# Saturn_Cartage.net
KiCad netlist of a schematic drawn in Altium Designer
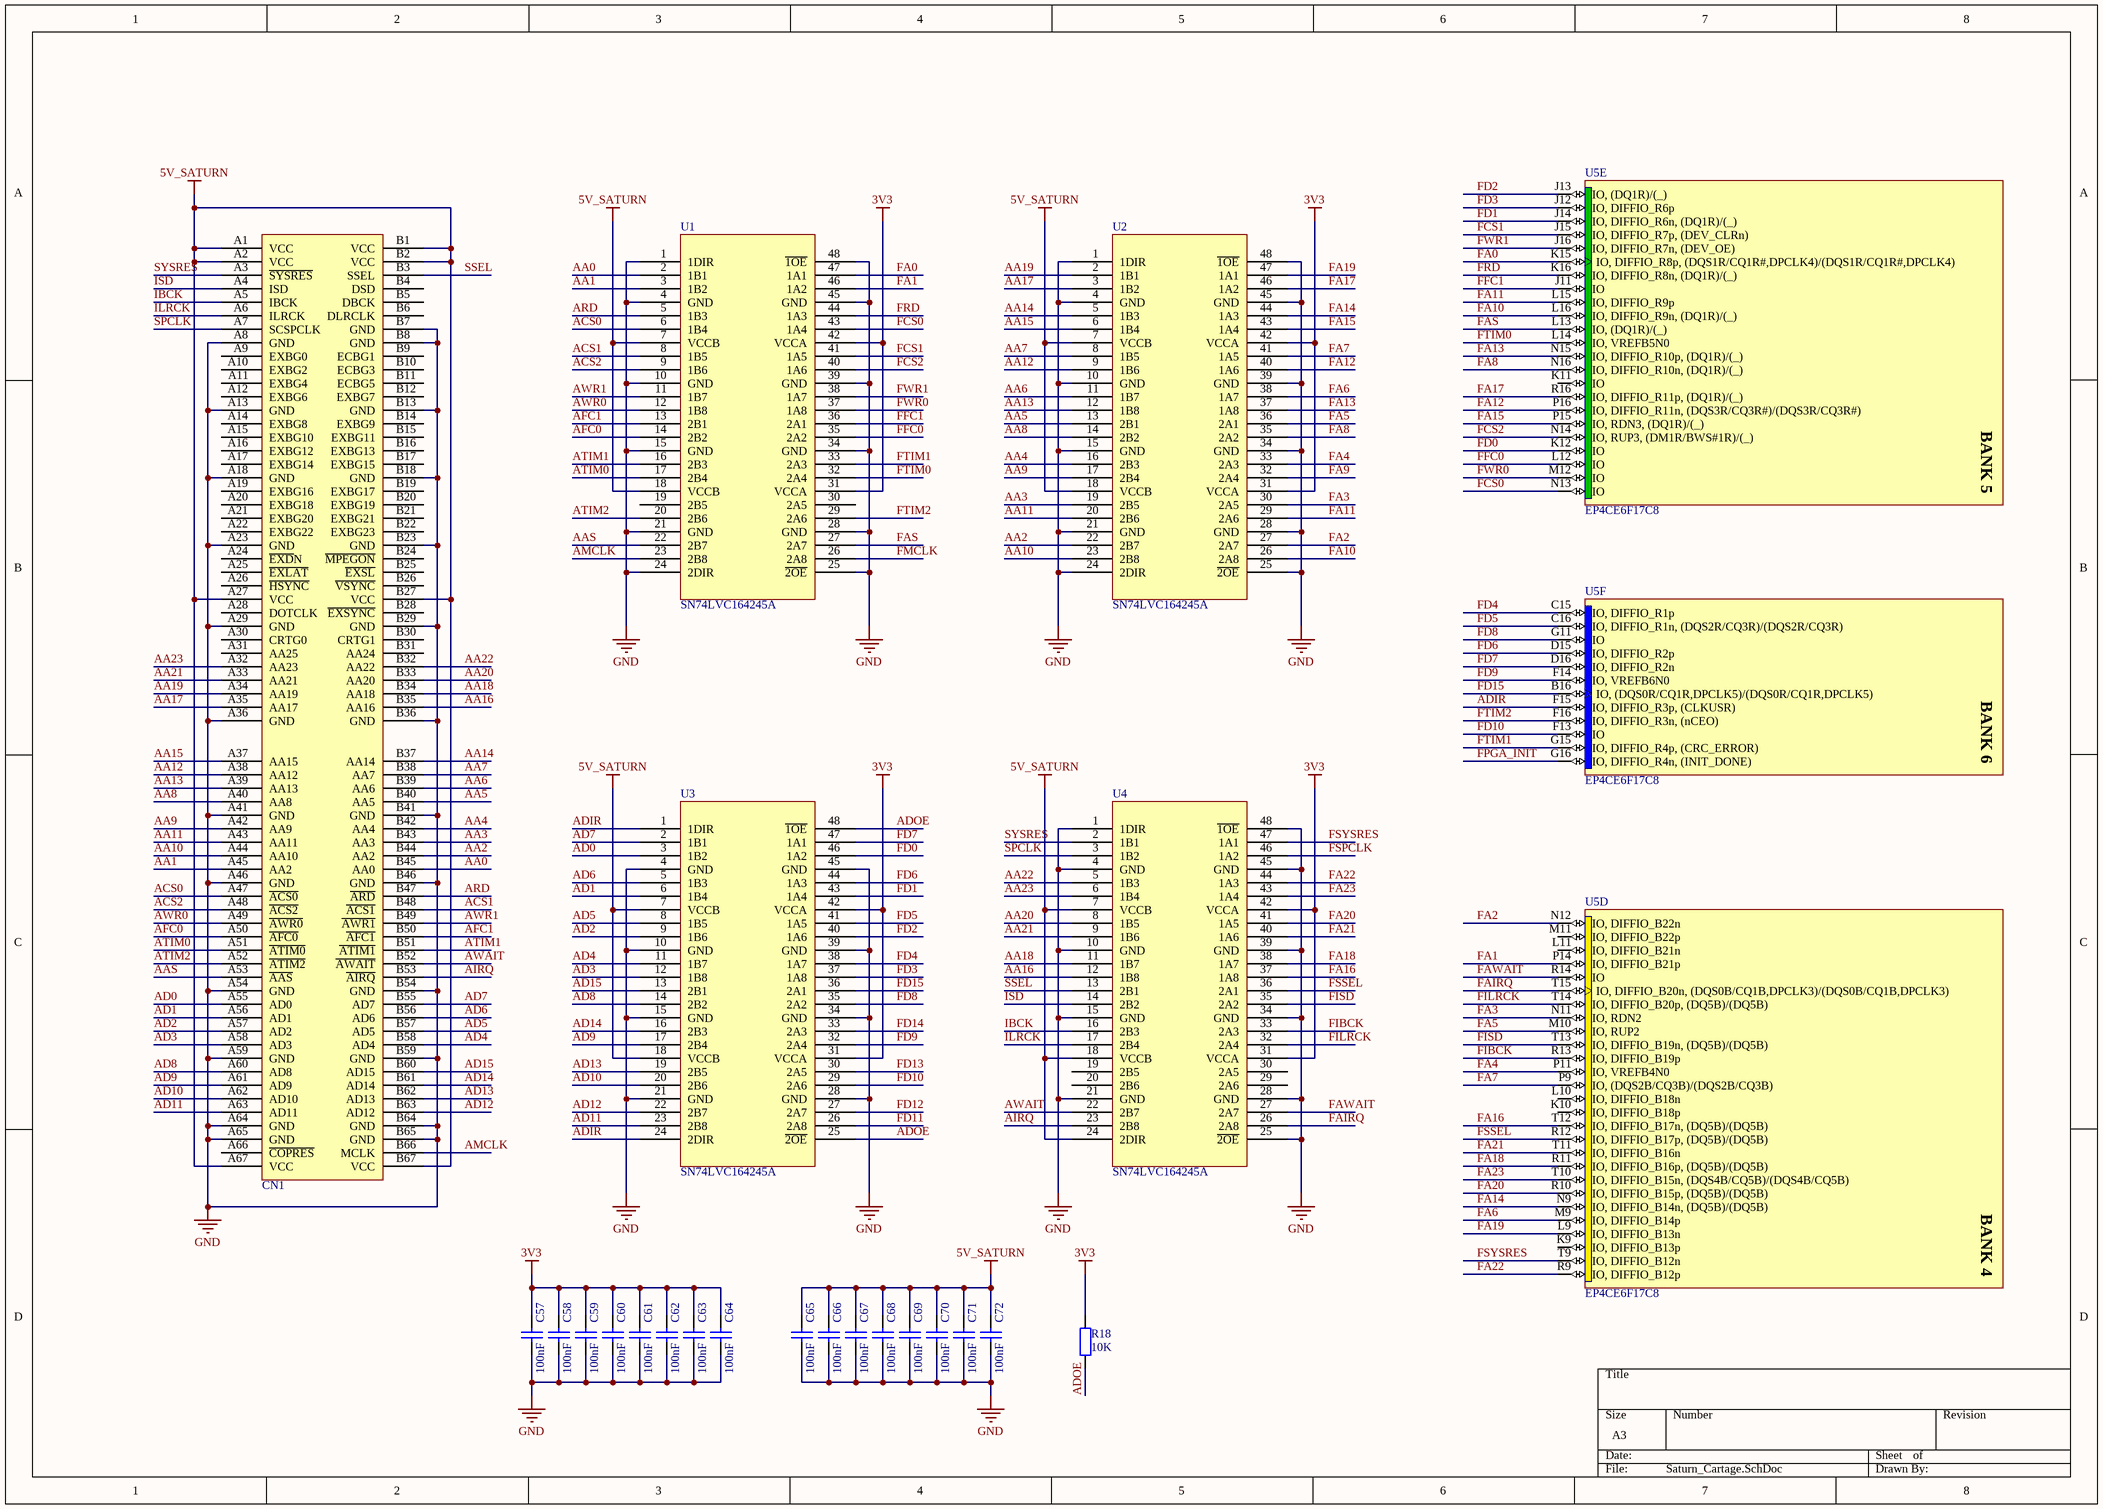
[diagram p0: Saturn_Cartage.SchDoc]

(export (version "E")
  (design (tool "Eeschema 10.0.6"))
  (components
    (comp (ref "C57")
      (value "100nF")
      (footprint "C0603")
      (description "Capacitor")
      (fields (field (name "PUBLISHER") "Altium Limited"))
      (libsource (lib "Miscellaneous Devices") (part "Cap"))
    )
    (comp (ref "C58")
      (value "100nF")
      (footprint "C0603")
      (description "Capacitor")
      (fields (field (name "PUBLISHER") "Altium Limited"))
      (libsource (lib "Miscellaneous Devices") (part "Cap"))
    )
    (comp (ref "C59")
      (value "100nF")
      (footprint "C0603")
      (description "Capacitor")
      (fields (field (name "PUBLISHER") "Altium Limited"))
      (libsource (lib "Miscellaneous Devices") (part "Cap"))
    )
    (comp (ref "C60")
      (value "100nF")
      (footprint "C0603")
      (description "Capacitor")
      (fields (field (name "PUBLISHER") "Altium Limited"))
      (libsource (lib "Miscellaneous Devices") (part "Cap"))
    )
    (comp (ref "C61")
      (value "100nF")
      (footprint "C0603")
      (description "Capacitor")
      (fields (field (name "PUBLISHER") "Altium Limited"))
      (libsource (lib "Miscellaneous Devices") (part "Cap"))
    )
    (comp (ref "C62")
      (value "100nF")
      (footprint "C0603")
      (description "Capacitor")
      (fields (field (name "PUBLISHER") "Altium Limited"))
      (libsource (lib "Miscellaneous Devices") (part "Cap"))
    )
    (comp (ref "C63")
      (value "100nF")
      (footprint "C0603")
      (description "Capacitor")
      (fields (field (name "PUBLISHER") "Altium Limited"))
      (libsource (lib "Miscellaneous Devices") (part "Cap"))
    )
    (comp (ref "C64")
      (value "100nF")
      (footprint "C0603")
      (description "Capacitor")
      (fields (field (name "PUBLISHER") "Altium Limited"))
      (libsource (lib "Miscellaneous Devices") (part "Cap"))
    )
    (comp (ref "C65")
      (value "100nF")
      (footprint "C0603")
      (description "Capacitor")
      (fields (field (name "PUBLISHER") "Altium Limited"))
      (libsource (lib "Miscellaneous Devices") (part "Cap"))
    )
    (comp (ref "C66")
      (value "100nF")
      (footprint "C0603")
      (description "Capacitor")
      (fields (field (name "PUBLISHER") "Altium Limited"))
      (libsource (lib "Miscellaneous Devices") (part "Cap"))
    )
    (comp (ref "C67")
      (value "100nF")
      (footprint "C0603")
      (description "Capacitor")
      (fields (field (name "PUBLISHER") "Altium Limited"))
      (libsource (lib "Miscellaneous Devices") (part "Cap"))
    )
    (comp (ref "C68")
      (value "100nF")
      (footprint "C0603")
      (description "Capacitor")
      (fields (field (name "PUBLISHER") "Altium Limited"))
      (libsource (lib "Miscellaneous Devices") (part "Cap"))
    )
    (comp (ref "C69")
      (value "100nF")
      (footprint "C0603")
      (description "Capacitor")
      (fields (field (name "PUBLISHER") "Altium Limited"))
      (libsource (lib "Miscellaneous Devices") (part "Cap"))
    )
    (comp (ref "C70")
      (value "100nF")
      (footprint "C0603")
      (description "Capacitor")
      (fields (field (name "PUBLISHER") "Altium Limited"))
      (libsource (lib "Miscellaneous Devices") (part "Cap"))
    )
    (comp (ref "C71")
      (value "100nF")
      (footprint "C0603")
      (description "Capacitor")
      (fields (field (name "PUBLISHER") "Altium Limited"))
      (libsource (lib "Miscellaneous Devices") (part "Cap"))
    )
    (comp (ref "C72")
      (value "100nF")
      (footprint "C0603")
      (description "Capacitor")
      (fields (field (name "PUBLISHER") "Altium Limited"))
      (libsource (lib "Miscellaneous Devices") (part "Cap"))
    )
    (comp (ref "CN1")
      (value "SaturnCartage")
      (footprint "Saturn_cart")
      (libsource (lib "ssmaster_1") (part "SaturnCartage"))
    )
    (comp (ref "R18")
      (value "10K")
      (footprint "R0603")
      (description "Resistor")
      (fields (field (name "PUBLISHER") "Altium Limited"))
      (libsource (lib "Miscellaneous Devices") (part "Res2"))
    )
    (comp (ref "U1")
      (value "SN74LVC164245A")
      (footprint "DGG048")
      (libsource (lib "ssmaster_1") (part "SN74LVC164245A"))
    )
    (comp (ref "U2")
      (value "SN74LVC164245A")
      (footprint "DGG048")
      (libsource (lib "ssmaster_1") (part "SN74LVC164245A"))
    )
    (comp (ref "U3")
      (value "SN74LVC164245A")
      (footprint "DGG048")
      (libsource (lib "ssmaster_1") (part "SN74LVC164245A"))
    )
    (comp (ref "U4")
      (value "SN74LVC164245A")
      (footprint "DGG048")
      (libsource (lib "ssmaster_1") (part "SN74LVC164245A"))
    )
    (comp (ref "U5")
      (value "EP4CE6F17C8")
      (footprint "FBGA256")
      (fields (field (name "PUBLISHER") "Altium Limited"))
      (libsource (lib "Altera Cyclone IV E") (part "EP4CE6F17C8"))
    )
  )
  (nets
    (net (code "1") (name "/AA0") (class "Default")
      (node (ref "CN1") (pin "B45") (pinfunction "AA0_B45") (pintype "passive"))
      (node (ref "U1") (pin "2") (pinfunction "1B1_2") (pintype "passive"))
    )
    (net (code "2") (name "/AA1") (class "Default")
      (node (ref "CN1") (pin "A45") (pinfunction "AA2_A45") (pintype "passive"))
      (node (ref "U1") (pin "3") (pinfunction "1B2_3") (pintype "passive"))
    )
    (net (code "3") (name "/AA2") (class "Default")
      (node (ref "CN1") (pin "B44") (pinfunction "AA2_B44") (pintype "passive"))
      (node (ref "U2") (pin "22") (pinfunction "2B7_22") (pintype "passive"))
    )
    (net (code "4") (name "/AA3") (class "Default")
      (node (ref "CN1") (pin "B43") (pinfunction "AA3_B43") (pintype "passive"))
      (node (ref "U2") (pin "19") (pinfunction "2B5_19") (pintype "passive"))
    )
    (net (code "5") (name "/AA4") (class "Default")
      (node (ref "CN1") (pin "B42") (pinfunction "AA4_B42") (pintype "passive"))
      (node (ref "U2") (pin "16") (pinfunction "2B3_16") (pintype "passive"))
    )
    (net (code "6") (name "/AA5") (class "Default")
      (node (ref "CN1") (pin "B40") (pinfunction "AA5_B40") (pintype "passive"))
      (node (ref "U2") (pin "13") (pinfunction "2B1_13") (pintype "passive"))
    )
    (net (code "7") (name "/AA6") (class "Default")
      (node (ref "CN1") (pin "B39") (pinfunction "AA6_B39") (pintype "passive"))
      (node (ref "U2") (pin "11") (pinfunction "1B7_11") (pintype "passive"))
    )
    (net (code "8") (name "/AA7") (class "Default")
      (node (ref "CN1") (pin "B38") (pinfunction "AA7_B38") (pintype "passive"))
      (node (ref "U2") (pin "8") (pinfunction "1B5_8") (pintype "passive"))
    )
    (net (code "9") (name "/AA8") (class "Default")
      (node (ref "CN1") (pin "A40") (pinfunction "AA8_A40") (pintype "passive"))
      (node (ref "U2") (pin "14") (pinfunction "2B2_14") (pintype "passive"))
    )
    (net (code "10") (name "/AA9") (class "Default")
      (node (ref "CN1") (pin "A42") (pinfunction "AA9_A42") (pintype "passive"))
      (node (ref "U2") (pin "17") (pinfunction "2B4_17") (pintype "passive"))
    )
    (net (code "11") (name "/AA10") (class "Default")
      (node (ref "CN1") (pin "A44") (pinfunction "AA10_A44") (pintype "passive"))
      (node (ref "U2") (pin "23") (pinfunction "2B8_23") (pintype "passive"))
    )
    (net (code "12") (name "/AA11") (class "Default")
      (node (ref "CN1") (pin "A43") (pinfunction "AA11_A43") (pintype "passive"))
      (node (ref "U2") (pin "20") (pinfunction "2B6_20") (pintype "passive"))
    )
    (net (code "13") (name "/AA12") (class "Default")
      (node (ref "CN1") (pin "A38") (pinfunction "AA12_A38") (pintype "passive"))
      (node (ref "U2") (pin "9") (pinfunction "1B6_9") (pintype "passive"))
    )
    (net (code "14") (name "/AA13") (class "Default")
      (node (ref "CN1") (pin "A39") (pinfunction "AA13_A39") (pintype "passive"))
      (node (ref "U2") (pin "12") (pinfunction "1B8_12") (pintype "passive"))
    )
    (net (code "15") (name "/AA14") (class "Default")
      (node (ref "CN1") (pin "B37") (pinfunction "AA14_B37") (pintype "passive"))
      (node (ref "U2") (pin "5") (pinfunction "1B3_5") (pintype "passive"))
    )
    (net (code "16") (name "/AA15") (class "Default")
      (node (ref "CN1") (pin "A37") (pinfunction "AA15_A37") (pintype "passive"))
      (node (ref "U2") (pin "6") (pinfunction "1B4_6") (pintype "passive"))
    )
    (net (code "17") (name "/AA16") (class "Default")
      (node (ref "CN1") (pin "B35") (pinfunction "AA16_B35") (pintype "passive"))
      (node (ref "U4") (pin "12") (pinfunction "1B8_12") (pintype "passive"))
    )
    (net (code "18") (name "/AA17") (class "Default")
      (node (ref "CN1") (pin "A35") (pinfunction "AA17_A35") (pintype "passive"))
      (node (ref "U2") (pin "3") (pinfunction "1B2_3") (pintype "passive"))
    )
    (net (code "19") (name "/AA18") (class "Default")
      (node (ref "CN1") (pin "B34") (pinfunction "AA18_B34") (pintype "passive"))
      (node (ref "U4") (pin "11") (pinfunction "1B7_11") (pintype "passive"))
    )
    (net (code "20") (name "/AA19") (class "Default")
      (node (ref "CN1") (pin "A34") (pinfunction "AA19_A34") (pintype "passive"))
      (node (ref "U2") (pin "2") (pinfunction "1B1_2") (pintype "passive"))
    )
    (net (code "21") (name "/AA20") (class "Default")
      (node (ref "CN1") (pin "B33") (pinfunction "AA20_B33") (pintype "passive"))
      (node (ref "U4") (pin "8") (pinfunction "1B5_8") (pintype "passive"))
    )
    (net (code "22") (name "/AA21") (class "Default")
      (node (ref "CN1") (pin "A33") (pinfunction "AA21_A33") (pintype "passive"))
      (node (ref "U4") (pin "9") (pinfunction "1B6_9") (pintype "passive"))
    )
    (net (code "23") (name "/AA22") (class "Default")
      (node (ref "CN1") (pin "B32") (pinfunction "AA22_B32") (pintype "passive"))
      (node (ref "U4") (pin "5") (pinfunction "1B3_5") (pintype "passive"))
    )
    (net (code "24") (name "/AA23") (class "Default")
      (node (ref "CN1") (pin "A32") (pinfunction "AA23_A32") (pintype "passive"))
      (node (ref "U4") (pin "6") (pinfunction "1B4_6") (pintype "passive"))
    )
    (net (code "25") (name "/AAS") (class "Default")
      (node (ref "CN1") (pin "A53") (pinfunction "~{AAS}_A53") (pintype "passive"))
      (node (ref "U1") (pin "22") (pinfunction "2B7_22") (pintype "passive"))
    )
    (net (code "26") (name "/ACS0") (class "Default")
      (node (ref "CN1") (pin "A47") (pinfunction "~{ACS0}_A47") (pintype "passive"))
      (node (ref "U1") (pin "6") (pinfunction "1B4_6") (pintype "passive"))
    )
    (net (code "27") (name "/ACS1") (class "Default")
      (node (ref "CN1") (pin "B48") (pinfunction "~{ACS1}_B48") (pintype "passive"))
      (node (ref "U1") (pin "8") (pinfunction "1B5_8") (pintype "passive"))
    )
    (net (code "28") (name "/ACS2") (class "Default")
      (node (ref "CN1") (pin "A48") (pinfunction "~{ACS2}_A48") (pintype "passive"))
      (node (ref "U1") (pin "9") (pinfunction "1B6_9") (pintype "passive"))
    )
    (net (code "29") (name "/AD0") (class "Default")
      (node (ref "CN1") (pin "A55") (pinfunction "AD0_A55") (pintype "passive"))
      (node (ref "U3") (pin "3") (pinfunction "1B2_3") (pintype "passive"))
    )
    (net (code "30") (name "/AD1") (class "Default")
      (node (ref "CN1") (pin "A56") (pinfunction "AD1_A56") (pintype "passive"))
      (node (ref "U3") (pin "6") (pinfunction "1B4_6") (pintype "passive"))
    )
    (net (code "31") (name "/AD2") (class "Default")
      (node (ref "CN1") (pin "A57") (pinfunction "AD2_A57") (pintype "passive"))
      (node (ref "U3") (pin "9") (pinfunction "1B6_9") (pintype "passive"))
    )
    (net (code "32") (name "/AD3") (class "Default")
      (node (ref "CN1") (pin "A58") (pinfunction "AD3_A58") (pintype "passive"))
      (node (ref "U3") (pin "12") (pinfunction "1B8_12") (pintype "passive"))
    )
    (net (code "33") (name "/AD4") (class "Default")
      (node (ref "CN1") (pin "B58") (pinfunction "AD4_B58") (pintype "passive"))
      (node (ref "U3") (pin "11") (pinfunction "1B7_11") (pintype "passive"))
    )
    (net (code "34") (name "/AD5") (class "Default")
      (node (ref "CN1") (pin "B57") (pinfunction "AD5_B57") (pintype "passive"))
      (node (ref "U3") (pin "8") (pinfunction "1B5_8") (pintype "passive"))
    )
    (net (code "35") (name "/AD6") (class "Default")
      (node (ref "CN1") (pin "B56") (pinfunction "AD6_B56") (pintype "passive"))
      (node (ref "U3") (pin "5") (pinfunction "1B3_5") (pintype "passive"))
    )
    (net (code "36") (name "/AD7") (class "Default")
      (node (ref "CN1") (pin "B55") (pinfunction "AD7_B55") (pintype "passive"))
      (node (ref "U3") (pin "2") (pinfunction "1B1_2") (pintype "passive"))
    )
    (net (code "37") (name "/AD8") (class "Default")
      (node (ref "CN1") (pin "A60") (pinfunction "AD8_A60") (pintype "passive"))
      (node (ref "U3") (pin "14") (pinfunction "2B2_14") (pintype "passive"))
    )
    (net (code "38") (name "/AD9") (class "Default")
      (node (ref "CN1") (pin "A61") (pinfunction "AD9_A61") (pintype "passive"))
      (node (ref "U3") (pin "17") (pinfunction "2B4_17") (pintype "passive"))
    )
    (net (code "39") (name "/AD10") (class "Default")
      (node (ref "CN1") (pin "A62") (pinfunction "AD10_A62") (pintype "passive"))
      (node (ref "U3") (pin "20") (pinfunction "2B6_20") (pintype "passive"))
    )
    (net (code "40") (name "/AD11") (class "Default")
      (node (ref "CN1") (pin "A63") (pinfunction "AD11_A63") (pintype "passive"))
      (node (ref "U3") (pin "23") (pinfunction "2B8_23") (pintype "passive"))
    )
    (net (code "41") (name "/AD12") (class "Default")
      (node (ref "CN1") (pin "B63") (pinfunction "AD12_B63") (pintype "passive"))
      (node (ref "U3") (pin "22") (pinfunction "2B7_22") (pintype "passive"))
    )
    (net (code "42") (name "/AD13") (class "Default")
      (node (ref "CN1") (pin "B62") (pinfunction "AD13_B62") (pintype "passive"))
      (node (ref "U3") (pin "19") (pinfunction "2B5_19") (pintype "passive"))
    )
    (net (code "43") (name "/AD14") (class "Default")
      (node (ref "CN1") (pin "B61") (pinfunction "AD14_B61") (pintype "passive"))
      (node (ref "U3") (pin "16") (pinfunction "2B3_16") (pintype "passive"))
    )
    (net (code "44") (name "/AD15") (class "Default")
      (node (ref "CN1") (pin "B60") (pinfunction "AD15_B60") (pintype "passive"))
      (node (ref "U3") (pin "13") (pinfunction "2B1_13") (pintype "passive"))
    )
    (net (code "45") (name "/ADIR") (class "Default")
      (node (ref "U3") (pin "1") (pinfunction "1DIR_1") (pintype "passive"))
      (node (ref "U3") (pin "24") (pinfunction "2DIR_24") (pintype "passive"))
      (node (ref "U5") (pin "F15") (pinfunction "IO,_DIFFIO_R3p,_(CLKUSR)_F15") (pintype "bidirectional"))
    )
    (net (code "46") (name "/ADOE") (class "Default")
      (node (ref "R18") (pin "1") (pinfunction "1_1") (pintype "passive"))
      (node (ref "U3") (pin "25") (pinfunction "~{2OE}_25") (pintype "passive"))
      (node (ref "U3") (pin "48") (pinfunction "~{1OE}_48") (pintype "passive"))
    )
    (net (code "47") (name "/AFC0") (class "Default")
      (node (ref "CN1") (pin "A50") (pinfunction "~{AFC0}_A50") (pintype "passive"))
      (node (ref "U1") (pin "14") (pinfunction "2B2_14") (pintype "passive"))
    )
    (net (code "48") (name "/AFC1") (class "Default")
      (node (ref "CN1") (pin "B50") (pinfunction "~{AFC1}_B50") (pintype "passive"))
      (node (ref "U1") (pin "13") (pinfunction "2B1_13") (pintype "passive"))
    )
    (net (code "49") (name "/AIRQ") (class "Default")
      (node (ref "CN1") (pin "B53") (pinfunction "~{AIRQ}_B53") (pintype "passive"))
      (node (ref "U4") (pin "23") (pinfunction "2B8_23") (pintype "passive"))
    )
    (net (code "50") (name "/AMCLK") (class "Default")
      (node (ref "CN1") (pin "B66") (pinfunction "MCLK_B66") (pintype "passive"))
      (node (ref "U1") (pin "23") (pinfunction "2B8_23") (pintype "passive"))
    )
    (net (code "51") (name "/ARD") (class "Default")
      (node (ref "CN1") (pin "B47") (pinfunction "~{ARD}_B47") (pintype "passive"))
      (node (ref "U1") (pin "5") (pinfunction "1B3_5") (pintype "passive"))
    )
    (net (code "52") (name "/ATIM0") (class "Default")
      (node (ref "CN1") (pin "A51") (pinfunction "~{ATIM0}_A51") (pintype "passive"))
      (node (ref "U1") (pin "17") (pinfunction "2B4_17") (pintype "passive"))
    )
    (net (code "53") (name "/ATIM1") (class "Default")
      (node (ref "CN1") (pin "B51") (pinfunction "~{ATIM1}_B51") (pintype "passive"))
      (node (ref "U1") (pin "16") (pinfunction "2B3_16") (pintype "passive"))
    )
    (net (code "54") (name "/ATIM2") (class "Default")
      (node (ref "CN1") (pin "A52") (pinfunction "~{ATIM2}_A52") (pintype "passive"))
      (node (ref "U1") (pin "20") (pinfunction "2B6_20") (pintype "passive"))
    )
    (net (code "55") (name "/AWAIT") (class "Default")
      (node (ref "CN1") (pin "B52") (pinfunction "~{AWAIT}_B52") (pintype "passive"))
      (node (ref "U4") (pin "22") (pinfunction "2B7_22") (pintype "passive"))
    )
    (net (code "56") (name "/AWR0") (class "Default")
      (node (ref "CN1") (pin "A49") (pinfunction "~{AWR0}_A49") (pintype "passive"))
      (node (ref "U1") (pin "12") (pinfunction "1B8_12") (pintype "passive"))
    )
    (net (code "57") (name "/AWR1") (class "Default")
      (node (ref "CN1") (pin "B49") (pinfunction "~{AWR1}_B49") (pintype "passive"))
      (node (ref "U1") (pin "11") (pinfunction "1B7_11") (pintype "passive"))
    )
    (net (code "58") (name "/FA0") (class "Default")
      (node (ref "U1") (pin "47") (pinfunction "1A1_47") (pintype "passive"))
      (node (ref "U5") (pin "K15") (pinfunction "IO,_DIFFIO_R8p,_(DQS1R/CQ1R#,DPCLK4)/(DQS1R/CQ1R#,DPCLK4)_K15") (pintype "bidirectional"))
    )
    (net (code "59") (name "/FA1") (class "Default")
      (node (ref "U1") (pin "46") (pinfunction "1A2_46") (pintype "power_in"))
      (node (ref "U5") (pin "P14") (pinfunction "IO,_DIFFIO_B21p_P14") (pintype "bidirectional"))
    )
    (net (code "60") (name "/FA2") (class "Default")
      (node (ref "U2") (pin "27") (pinfunction "2A7_27") (pintype "passive"))
      (node (ref "U5") (pin "N12") (pinfunction "IO,_DIFFIO_B22n_N12") (pintype "bidirectional"))
    )
    (net (code "61") (name "/FA3") (class "Default")
      (node (ref "U2") (pin "30") (pinfunction "2A5_30") (pintype "passive"))
      (node (ref "U5") (pin "N11") (pinfunction "IO,_RDN2_N11") (pintype "bidirectional"))
    )
    (net (code "62") (name "/FA4") (class "Default")
      (node (ref "U2") (pin "33") (pinfunction "2A3_33") (pintype "passive"))
      (node (ref "U5") (pin "P11") (pinfunction "IO,_VREFB4N0_P11") (pintype "bidirectional"))
    )
    (net (code "63") (name "/FA5") (class "Default")
      (node (ref "U2") (pin "36") (pinfunction "2A1_36") (pintype "passive"))
      (node (ref "U5") (pin "M10") (pinfunction "IO,_RUP2_M10") (pintype "bidirectional"))
    )
    (net (code "64") (name "/FA6") (class "Default")
      (node (ref "U2") (pin "38") (pinfunction "1A7_38") (pintype "passive"))
      (node (ref "U5") (pin "M9") (pinfunction "IO,_DIFFIO_B14p_M9") (pintype "bidirectional"))
    )
    (net (code "65") (name "/FA7") (class "Default")
      (node (ref "U2") (pin "41") (pinfunction "1A5_41") (pintype "passive"))
      (node (ref "U5") (pin "P9") (pinfunction "IO,_(DQS2B/CQ3B)/(DQS2B/CQ3B)_P9") (pintype "bidirectional"))
    )
    (net (code "66") (name "/FA8") (class "Default")
      (node (ref "U2") (pin "35") (pinfunction "2A2_35") (pintype "passive"))
      (node (ref "U5") (pin "N16") (pinfunction "IO,_DIFFIO_R10n,_(DQ1R)/(_)_N16") (pintype "bidirectional"))
    )
    (net (code "67") (name "/FA9") (class "Default")
      (node (ref "U2") (pin "32") (pinfunction "2A4_32") (pintype "passive"))
    )
    (net (code "68") (name "/FA10") (class "Default")
      (node (ref "U2") (pin "26") (pinfunction "2A8_26") (pintype "passive"))
      (node (ref "U5") (pin "L16") (pinfunction "IO,_DIFFIO_R9n,_(DQ1R)/(_)_L16") (pintype "bidirectional"))
    )
    (net (code "69") (name "/FA11") (class "Default")
      (node (ref "U2") (pin "29") (pinfunction "2A6_29") (pintype "passive"))
      (node (ref "U5") (pin "L15") (pinfunction "IO,_DIFFIO_R9p_L15") (pintype "bidirectional"))
    )
    (net (code "70") (name "/FA12") (class "Default")
      (node (ref "U2") (pin "40") (pinfunction "1A6_40") (pintype "passive"))
      (node (ref "U5") (pin "P16") (pinfunction "IO,_DIFFIO_R11n,_(DQS3R/CQ3R#)/(DQS3R/CQ3R#)_P16") (pintype "bidirectional"))
    )
    (net (code "71") (name "/FA13") (class "Default")
      (node (ref "U2") (pin "37") (pinfunction "1A8_37") (pintype "passive"))
      (node (ref "U5") (pin "N15") (pinfunction "IO,_DIFFIO_R10p,_(DQ1R)/(_)_N15") (pintype "bidirectional"))
    )
    (net (code "72") (name "/FA14") (class "Default")
      (node (ref "U2") (pin "44") (pinfunction "1A3_44") (pintype "passive"))
      (node (ref "U5") (pin "N9") (pinfunction "IO,_DIFFIO_B14n,_(DQ5B)/(DQ5B)_N9") (pintype "bidirectional"))
    )
    (net (code "73") (name "/FA15") (class "Default")
      (node (ref "U2") (pin "43") (pinfunction "1A4_43") (pintype "passive"))
      (node (ref "U5") (pin "P15") (pinfunction "IO,_RDN3,_(DQ1R)/(_)_P15") (pintype "bidirectional"))
    )
    (net (code "74") (name "/FA16") (class "Default")
      (node (ref "U4") (pin "37") (pinfunction "1A8_37") (pintype "passive"))
      (node (ref "U5") (pin "T12") (pinfunction "IO,_DIFFIO_B17n,_(DQ5B)/(DQ5B)_T12") (pintype "bidirectional"))
    )
    (net (code "75") (name "/FA17") (class "Default")
      (node (ref "U2") (pin "46") (pinfunction "1A2_46") (pintype "power_in"))
      (node (ref "U5") (pin "R16") (pinfunction "IO,_DIFFIO_R11p,_(DQ1R)/(_)_R16") (pintype "bidirectional"))
    )
    (net (code "76") (name "/FA18") (class "Default")
      (node (ref "U4") (pin "38") (pinfunction "1A7_38") (pintype "passive"))
      (node (ref "U5") (pin "R11") (pinfunction "IO,_DIFFIO_B16p,_(DQ5B)/(DQ5B)_R11") (pintype "bidirectional"))
    )
    (net (code "77") (name "/FA19") (class "Default")
      (node (ref "U2") (pin "47") (pinfunction "1A1_47") (pintype "passive"))
      (node (ref "U5") (pin "L9") (pinfunction "IO,_DIFFIO_B13n_L9") (pintype "bidirectional"))
    )
    (net (code "78") (name "/FA20") (class "Default")
      (node (ref "U4") (pin "41") (pinfunction "1A5_41") (pintype "passive"))
      (node (ref "U5") (pin "R10") (pinfunction "IO,_DIFFIO_B15p,_(DQ5B)/(DQ5B)_R10") (pintype "bidirectional"))
    )
    (net (code "79") (name "/FA21") (class "Default")
      (node (ref "U4") (pin "40") (pinfunction "1A6_40") (pintype "passive"))
      (node (ref "U5") (pin "T11") (pinfunction "IO,_DIFFIO_B16n_T11") (pintype "bidirectional"))
    )
    (net (code "80") (name "/FA22") (class "Default")
      (node (ref "U4") (pin "44") (pinfunction "1A3_44") (pintype "passive"))
      (node (ref "U5") (pin "R9") (pinfunction "IO,_DIFFIO_B12p_R9") (pintype "bidirectional"))
    )
    (net (code "81") (name "/FA23") (class "Default")
      (node (ref "U4") (pin "43") (pinfunction "1A4_43") (pintype "passive"))
      (node (ref "U5") (pin "T10") (pinfunction "IO,_DIFFIO_B15n,_(DQS4B/CQ5B)/(DQS4B/CQ5B)_T10") (pintype "bidirectional"))
    )
    (net (code "82") (name "/FAIRQ") (class "Default")
      (node (ref "U4") (pin "26") (pinfunction "2A8_26") (pintype "passive"))
      (node (ref "U5") (pin "T15") (pinfunction "IO,_DIFFIO_B20n,_(DQS0B/CQ1B,DPCLK3)/(DQS0B/CQ1B,DPCLK3)_T15") (pintype "bidirectional"))
    )
    (net (code "83") (name "/FAS") (class "Default")
      (node (ref "U1") (pin "27") (pinfunction "2A7_27") (pintype "passive"))
      (node (ref "U5") (pin "L13") (pinfunction "IO,_(DQ1R)/(_)_L13") (pintype "bidirectional"))
    )
    (net (code "84") (name "/FAWAIT") (class "Default")
      (node (ref "U4") (pin "27") (pinfunction "2A7_27") (pintype "passive"))
      (node (ref "U5") (pin "R14") (pinfunction "IO_R14") (pintype "bidirectional"))
    )
    (net (code "85") (name "/FCS0") (class "Default")
      (node (ref "U1") (pin "43") (pinfunction "1A4_43") (pintype "passive"))
      (node (ref "U5") (pin "N13") (pinfunction "IO_N13") (pintype "bidirectional"))
    )
    (net (code "86") (name "/FCS1") (class "Default")
      (node (ref "U1") (pin "41") (pinfunction "1A5_41") (pintype "passive"))
      (node (ref "U5") (pin "J15") (pinfunction "IO,_DIFFIO_R7p,_(DEV_CLRn)_J15") (pintype "bidirectional"))
    )
    (net (code "87") (name "/FCS2") (class "Default")
      (node (ref "U1") (pin "40") (pinfunction "1A6_40") (pintype "passive"))
      (node (ref "U5") (pin "N14") (pinfunction "IO,_RUP3,_(DM1R/BWS#1R)/(_)_N14") (pintype "bidirectional"))
    )
    (net (code "88") (name "/FD0") (class "Default")
      (node (ref "U3") (pin "46") (pinfunction "1A2_46") (pintype "power_in"))
      (node (ref "U5") (pin "K12") (pinfunction "IO_K12") (pintype "bidirectional"))
    )
    (net (code "89") (name "/FD1") (class "Default")
      (node (ref "U3") (pin "43") (pinfunction "1A4_43") (pintype "passive"))
      (node (ref "U5") (pin "J14") (pinfunction "IO,_DIFFIO_R6n,_(DQ1R)/(_)_J14") (pintype "bidirectional"))
    )
    (net (code "90") (name "/FD2") (class "Default")
      (node (ref "U3") (pin "40") (pinfunction "1A6_40") (pintype "passive"))
      (node (ref "U5") (pin "J13") (pinfunction "IO,_(DQ1R)/(_)_J13") (pintype "bidirectional"))
    )
    (net (code "91") (name "/FD3") (class "Default")
      (node (ref "U3") (pin "37") (pinfunction "1A8_37") (pintype "passive"))
      (node (ref "U5") (pin "J12") (pinfunction "IO,_DIFFIO_R6p_J12") (pintype "bidirectional"))
    )
    (net (code "92") (name "/FD4") (class "Default")
      (node (ref "U3") (pin "38") (pinfunction "1A7_38") (pintype "passive"))
      (node (ref "U5") (pin "C15") (pinfunction "IO,_DIFFIO_R1p_C15") (pintype "bidirectional"))
    )
    (net (code "93") (name "/FD5") (class "Default")
      (node (ref "U3") (pin "41") (pinfunction "1A5_41") (pintype "passive"))
      (node (ref "U5") (pin "C16") (pinfunction "IO,_DIFFIO_R1n,_(DQS2R/CQ3R)/(DQS2R/CQ3R)_C16") (pintype "bidirectional"))
    )
    (net (code "94") (name "/FD6") (class "Default")
      (node (ref "U3") (pin "44") (pinfunction "1A3_44") (pintype "passive"))
      (node (ref "U5") (pin "D15") (pinfunction "IO,_DIFFIO_R2p_D15") (pintype "bidirectional"))
    )
    (net (code "95") (name "/FD7") (class "Default")
      (node (ref "U3") (pin "47") (pinfunction "1A1_47") (pintype "passive"))
      (node (ref "U5") (pin "D16") (pinfunction "IO,_DIFFIO_R2n_D16") (pintype "bidirectional"))
    )
    (net (code "96") (name "/FD8") (class "Default")
      (node (ref "U3") (pin "35") (pinfunction "2A2_35") (pintype "passive"))
      (node (ref "U5") (pin "G11") (pinfunction "IO_G11") (pintype "bidirectional"))
    )
    (net (code "97") (name "/FD9") (class "Default")
      (node (ref "U3") (pin "32") (pinfunction "2A4_32") (pintype "passive"))
      (node (ref "U5") (pin "F14") (pinfunction "IO,_VREFB6N0_F14") (pintype "bidirectional"))
    )
    (net (code "98") (name "/FD10") (class "Default")
      (node (ref "U3") (pin "29") (pinfunction "2A6_29") (pintype "passive"))
      (node (ref "U5") (pin "F13") (pinfunction "IO_F13") (pintype "bidirectional"))
    )
    (net (code "99") (name "/FD11") (class "Default")
      (node (ref "U3") (pin "26") (pinfunction "2A8_26") (pintype "passive"))
    )
    (net (code "100") (name "/FD12") (class "Default")
      (node (ref "U3") (pin "27") (pinfunction "2A7_27") (pintype "passive"))
    )
    (net (code "101") (name "/FD13") (class "Default")
      (node (ref "U3") (pin "30") (pinfunction "2A5_30") (pintype "passive"))
    )
    (net (code "102") (name "/FD14") (class "Default")
      (node (ref "U3") (pin "33") (pinfunction "2A3_33") (pintype "passive"))
    )
    (net (code "103") (name "/FD15") (class "Default")
      (node (ref "U3") (pin "36") (pinfunction "2A1_36") (pintype "passive"))
      (node (ref "U5") (pin "B16") (pinfunction "IO,_(DQS0R/CQ1R,DPCLK5)/(DQS0R/CQ1R,DPCLK5)_B16") (pintype "bidirectional"))
    )
    (net (code "104") (name "/FFC0") (class "Default")
      (node (ref "U1") (pin "35") (pinfunction "2A2_35") (pintype "passive"))
      (node (ref "U5") (pin "L12") (pinfunction "IO_L12") (pintype "bidirectional"))
    )
    (net (code "105") (name "/FFC1") (class "Default")
      (node (ref "U1") (pin "36") (pinfunction "2A1_36") (pintype "passive"))
      (node (ref "U5") (pin "J11") (pinfunction "IO_J11") (pintype "bidirectional"))
    )
    (net (code "106") (name "/FIBCK") (class "Default")
      (node (ref "U4") (pin "33") (pinfunction "2A3_33") (pintype "passive"))
      (node (ref "U5") (pin "R13") (pinfunction "IO,_DIFFIO_B19p_R13") (pintype "bidirectional"))
    )
    (net (code "107") (name "/FILRCK") (class "Default")
      (node (ref "U4") (pin "32") (pinfunction "2A4_32") (pintype "passive"))
      (node (ref "U5") (pin "T14") (pinfunction "IO,_DIFFIO_B20p,_(DQ5B)/(DQ5B)_T14") (pintype "bidirectional"))
    )
    (net (code "108") (name "/FISD") (class "Default")
      (node (ref "U4") (pin "35") (pinfunction "2A2_35") (pintype "passive"))
      (node (ref "U5") (pin "T13") (pinfunction "IO,_DIFFIO_B19n,_(DQ5B)/(DQ5B)_T13") (pintype "bidirectional"))
    )
    (net (code "109") (name "/FMCLK") (class "Default")
      (node (ref "U1") (pin "26") (pinfunction "2A8_26") (pintype "passive"))
    )
    (net (code "110") (name "/FPGA_INIT") (class "Default")
      (node (ref "U5") (pin "G16") (pinfunction "IO,_DIFFIO_R4n,_(INIT_DONE)_G16") (pintype "bidirectional"))
    )
    (net (code "111") (name "/FRD") (class "Default")
      (node (ref "U1") (pin "44") (pinfunction "1A3_44") (pintype "passive"))
      (node (ref "U5") (pin "K16") (pinfunction "IO,_DIFFIO_R8n,_(DQ1R)/(_)_K16") (pintype "bidirectional"))
    )
    (net (code "112") (name "/FSPCLK") (class "Default")
      (node (ref "U4") (pin "46") (pinfunction "1A2_46") (pintype "power_in"))
    )
    (net (code "113") (name "/FSSEL") (class "Default")
      (node (ref "U4") (pin "36") (pinfunction "2A1_36") (pintype "passive"))
      (node (ref "U5") (pin "R12") (pinfunction "IO,_DIFFIO_B17p,_(DQ5B)/(DQ5B)_R12") (pintype "bidirectional"))
    )
    (net (code "114") (name "/FSYSRES") (class "Default")
      (node (ref "U4") (pin "47") (pinfunction "1A1_47") (pintype "passive"))
      (node (ref "U5") (pin "T9") (pinfunction "IO,_DIFFIO_B12n_T9") (pintype "bidirectional"))
    )
    (net (code "115") (name "/FTIM0") (class "Default")
      (node (ref "U1") (pin "32") (pinfunction "2A4_32") (pintype "passive"))
      (node (ref "U5") (pin "L14") (pinfunction "IO,_VREFB5N0_L14") (pintype "bidirectional"))
    )
    (net (code "116") (name "/FTIM1") (class "Default")
      (node (ref "U1") (pin "33") (pinfunction "2A3_33") (pintype "passive"))
      (node (ref "U5") (pin "G15") (pinfunction "IO,_DIFFIO_R4p,_(CRC_ERROR)_G15") (pintype "bidirectional"))
    )
    (net (code "117") (name "/FTIM2") (class "Default")
      (node (ref "U1") (pin "29") (pinfunction "2A6_29") (pintype "passive"))
      (node (ref "U5") (pin "F16") (pinfunction "IO,_DIFFIO_R3n,_(nCEO)_F16") (pintype "bidirectional"))
    )
    (net (code "118") (name "/FWR0") (class "Default")
      (node (ref "U1") (pin "37") (pinfunction "1A8_37") (pintype "passive"))
      (node (ref "U5") (pin "M12") (pinfunction "IO_M12") (pintype "bidirectional"))
    )
    (net (code "119") (name "/FWR1") (class "Default")
      (node (ref "U1") (pin "38") (pinfunction "1A7_38") (pintype "passive"))
      (node (ref "U5") (pin "J16") (pinfunction "IO,_DIFFIO_R7n,_(DEV_OE)_J16") (pintype "bidirectional"))
    )
    (net (code "120") (name "/IBCK") (class "Default")
      (node (ref "CN1") (pin "A5") (pinfunction "IBCK_A5") (pintype "passive"))
      (node (ref "U4") (pin "16") (pinfunction "2B3_16") (pintype "passive"))
    )
    (net (code "121") (name "/ILRCK") (class "Default")
      (node (ref "CN1") (pin "A6") (pinfunction "ILRCK_A6") (pintype "passive"))
      (node (ref "U4") (pin "17") (pinfunction "2B4_17") (pintype "passive"))
    )
    (net (code "122") (name "/ISD") (class "Default")
      (node (ref "CN1") (pin "A4") (pinfunction "ISD_A4") (pintype "passive"))
      (node (ref "U4") (pin "14") (pinfunction "2B2_14") (pintype "passive"))
    )
    (net (code "123") (name "/SPCLK") (class "Default")
      (node (ref "CN1") (pin "A7") (pinfunction "SCSPCLK_A7") (pintype "passive"))
      (node (ref "U4") (pin "3") (pinfunction "1B2_3") (pintype "passive"))
    )
    (net (code "124") (name "/SSEL") (class "Default")
      (node (ref "CN1") (pin "B3") (pinfunction "SSEL_B3") (pintype "passive"))
      (node (ref "U4") (pin "13") (pinfunction "2B1_13") (pintype "passive"))
    )
    (net (code "125") (name "/SYSRES") (class "Default")
      (node (ref "CN1") (pin "A3") (pinfunction "~{SYSRES}_A3") (pintype "passive"))
      (node (ref "U4") (pin "2") (pinfunction "1B1_2") (pintype "passive"))
    )
    (net (code "126") (name "3V3") (class "Default")
      (node (ref "C57") (pin "2") (pinfunction "2_2") (pintype "passive"))
      (node (ref "C58") (pin "2") (pinfunction "2_2") (pintype "passive"))
      (node (ref "C59") (pin "2") (pinfunction "2_2") (pintype "passive"))
      (node (ref "C60") (pin "2") (pinfunction "2_2") (pintype "passive"))
      (node (ref "C61") (pin "2") (pinfunction "2_2") (pintype "passive"))
      (node (ref "C62") (pin "2") (pinfunction "2_2") (pintype "passive"))
      (node (ref "C63") (pin "2") (pinfunction "2_2") (pintype "passive"))
      (node (ref "C64") (pin "2") (pinfunction "2_2") (pintype "passive"))
      (node (ref "R18") (pin "2") (pinfunction "2_2") (pintype "passive"))
      (node (ref "U1") (pin "31") (pinfunction "VCCA_31") (pintype "power_in"))
      (node (ref "U1") (pin "42") (pinfunction "VCCA_42") (pintype "power_in"))
      (node (ref "U2") (pin "31") (pinfunction "VCCA_31") (pintype "power_in"))
      (node (ref "U2") (pin "42") (pinfunction "VCCA_42") (pintype "power_in"))
      (node (ref "U3") (pin "31") (pinfunction "VCCA_31") (pintype "power_in"))
      (node (ref "U3") (pin "42") (pinfunction "VCCA_42") (pintype "power_in"))
      (node (ref "U4") (pin "31") (pinfunction "VCCA_31") (pintype "power_in"))
      (node (ref "U4") (pin "42") (pinfunction "VCCA_42") (pintype "power_in"))
    )
    (net (code "127") (name "5V_SATURN") (class "Default")
      (node (ref "C65") (pin "2") (pinfunction "2_2") (pintype "passive"))
      (node (ref "C66") (pin "2") (pinfunction "2_2") (pintype "passive"))
      (node (ref "C67") (pin "2") (pinfunction "2_2") (pintype "passive"))
      (node (ref "C68") (pin "2") (pinfunction "2_2") (pintype "passive"))
      (node (ref "C69") (pin "2") (pinfunction "2_2") (pintype "passive"))
      (node (ref "C70") (pin "2") (pinfunction "2_2") (pintype "passive"))
      (node (ref "C71") (pin "2") (pinfunction "2_2") (pintype "passive"))
      (node (ref "C72") (pin "2") (pinfunction "2_2") (pintype "passive"))
      (node (ref "CN1") (pin "A1") (pinfunction "VCC_A1") (pintype "passive"))
      (node (ref "CN1") (pin "A2") (pinfunction "VCC_A2") (pintype "passive"))
      (node (ref "CN1") (pin "A27") (pinfunction "VCC_A27") (pintype "passive"))
      (node (ref "CN1") (pin "A67") (pinfunction "VCC_A67") (pintype "passive"))
      (node (ref "CN1") (pin "B1") (pinfunction "VCC_B1") (pintype "passive"))
      (node (ref "CN1") (pin "B2") (pinfunction "VCC_B2") (pintype "passive"))
      (node (ref "CN1") (pin "B27") (pinfunction "VCC_B27") (pintype "passive"))
      (node (ref "CN1") (pin "B67") (pinfunction "VCC_B67") (pintype "passive"))
      (node (ref "U1") (pin "18") (pinfunction "VCCB_18") (pintype "power_in"))
      (node (ref "U1") (pin "7") (pinfunction "VCCB_7") (pintype "power_in"))
      (node (ref "U2") (pin "18") (pinfunction "VCCB_18") (pintype "power_in"))
      (node (ref "U2") (pin "7") (pinfunction "VCCB_7") (pintype "power_in"))
      (node (ref "U3") (pin "18") (pinfunction "VCCB_18") (pintype "power_in"))
      (node (ref "U3") (pin "7") (pinfunction "VCCB_7") (pintype "power_in"))
      (node (ref "U4") (pin "18") (pinfunction "VCCB_18") (pintype "power_in"))
      (node (ref "U4") (pin "24") (pinfunction "2DIR_24") (pintype "passive"))
      (node (ref "U4") (pin "7") (pinfunction "VCCB_7") (pintype "power_in"))
    )
    (net (code "128") (name "GND") (class "Default")
      (node (ref "C57") (pin "1") (pinfunction "1_1") (pintype "passive"))
      (node (ref "C58") (pin "1") (pinfunction "1_1") (pintype "passive"))
      (node (ref "C59") (pin "1") (pinfunction "1_1") (pintype "passive"))
      (node (ref "C60") (pin "1") (pinfunction "1_1") (pintype "passive"))
      (node (ref "C61") (pin "1") (pinfunction "1_1") (pintype "passive"))
      (node (ref "C62") (pin "1") (pinfunction "1_1") (pintype "passive"))
      (node (ref "C63") (pin "1") (pinfunction "1_1") (pintype "passive"))
      (node (ref "C64") (pin "1") (pinfunction "1_1") (pintype "passive"))
      (node (ref "C65") (pin "1") (pinfunction "1_1") (pintype "passive"))
      (node (ref "C66") (pin "1") (pinfunction "1_1") (pintype "passive"))
      (node (ref "C67") (pin "1") (pinfunction "1_1") (pintype "passive"))
      (node (ref "C68") (pin "1") (pinfunction "1_1") (pintype "passive"))
      (node (ref "C69") (pin "1") (pinfunction "1_1") (pintype "passive"))
      (node (ref "C70") (pin "1") (pinfunction "1_1") (pintype "passive"))
      (node (ref "C71") (pin "1") (pinfunction "1_1") (pintype "passive"))
      (node (ref "C72") (pin "1") (pinfunction "1_1") (pintype "passive"))
      (node (ref "CN1") (pin "A13") (pinfunction "GND_A13") (pintype "passive"))
      (node (ref "CN1") (pin "A18") (pinfunction "GND_A18") (pintype "passive"))
      (node (ref "CN1") (pin "A23") (pinfunction "GND_A23") (pintype "passive"))
      (node (ref "CN1") (pin "A29") (pinfunction "GND_A29") (pintype "passive"))
      (node (ref "CN1") (pin "A36") (pinfunction "GND_A36") (pintype "passive"))
      (node (ref "CN1") (pin "A41") (pinfunction "GND_A41") (pintype "passive"))
      (node (ref "CN1") (pin "A46") (pinfunction "GND_A46") (pintype "passive"))
      (node (ref "CN1") (pin "A54") (pinfunction "GND_A54") (pintype "passive"))
      (node (ref "CN1") (pin "A59") (pinfunction "GND_A59") (pintype "passive"))
      (node (ref "CN1") (pin "A64") (pinfunction "GND_A64") (pintype "passive"))
      (node (ref "CN1") (pin "A65") (pinfunction "GND_A65") (pintype "passive"))
      (node (ref "CN1") (pin "A8") (pinfunction "GND_A8") (pintype "passive"))
      (node (ref "CN1") (pin "B13") (pinfunction "GND_B13") (pintype "passive"))
      (node (ref "CN1") (pin "B18") (pinfunction "GND_B18") (pintype "passive"))
      (node (ref "CN1") (pin "B23") (pinfunction "GND_B23") (pintype "passive"))
      (node (ref "CN1") (pin "B29") (pinfunction "GND_B29") (pintype "passive"))
      (node (ref "CN1") (pin "B36") (pinfunction "GND_B36") (pintype "passive"))
      (node (ref "CN1") (pin "B41") (pinfunction "GND_B41") (pintype "passive"))
      (node (ref "CN1") (pin "B46") (pinfunction "GND_B46") (pintype "passive"))
      (node (ref "CN1") (pin "B54") (pinfunction "GND_B54") (pintype "passive"))
      (node (ref "CN1") (pin "B59") (pinfunction "GND_B59") (pintype "passive"))
      (node (ref "CN1") (pin "B64") (pinfunction "GND_B64") (pintype "passive"))
      (node (ref "CN1") (pin "B65") (pinfunction "GND_B65") (pintype "passive"))
      (node (ref "CN1") (pin "B7") (pinfunction "GND_B7") (pintype "passive"))
      (node (ref "CN1") (pin "B8") (pinfunction "GND_B8") (pintype "passive"))
      (node (ref "U1") (pin "1") (pinfunction "1DIR_1") (pintype "passive"))
      (node (ref "U1") (pin "10") (pinfunction "GND_10") (pintype "power_in"))
      (node (ref "U1") (pin "15") (pinfunction "GND_15") (pintype "power_in"))
      (node (ref "U1") (pin "21") (pinfunction "GND_21") (pintype "power_in"))
      (node (ref "U1") (pin "24") (pinfunction "2DIR_24") (pintype "passive"))
      (node (ref "U1") (pin "25") (pinfunction "~{2OE}_25") (pintype "passive"))
      (node (ref "U1") (pin "28") (pinfunction "GND_28") (pintype "power_in"))
      (node (ref "U1") (pin "34") (pinfunction "GND_34") (pintype "power_in"))
      (node (ref "U1") (pin "39") (pinfunction "GND_39") (pintype "power_in"))
      (node (ref "U1") (pin "4") (pinfunction "GND_4") (pintype "power_in"))
      (node (ref "U1") (pin "45") (pinfunction "GND_45") (pintype "power_in"))
      (node (ref "U1") (pin "48") (pinfunction "~{1OE}_48") (pintype "passive"))
      (node (ref "U2") (pin "1") (pinfunction "1DIR_1") (pintype "passive"))
      (node (ref "U2") (pin "10") (pinfunction "GND_10") (pintype "power_in"))
      (node (ref "U2") (pin "15") (pinfunction "GND_15") (pintype "power_in"))
      (node (ref "U2") (pin "21") (pinfunction "GND_21") (pintype "power_in"))
      (node (ref "U2") (pin "24") (pinfunction "2DIR_24") (pintype "passive"))
      (node (ref "U2") (pin "25") (pinfunction "~{2OE}_25") (pintype "passive"))
      (node (ref "U2") (pin "28") (pinfunction "GND_28") (pintype "power_in"))
      (node (ref "U2") (pin "34") (pinfunction "GND_34") (pintype "power_in"))
      (node (ref "U2") (pin "39") (pinfunction "GND_39") (pintype "power_in"))
      (node (ref "U2") (pin "4") (pinfunction "GND_4") (pintype "power_in"))
      (node (ref "U2") (pin "45") (pinfunction "GND_45") (pintype "power_in"))
      (node (ref "U2") (pin "48") (pinfunction "~{1OE}_48") (pintype "passive"))
      (node (ref "U3") (pin "10") (pinfunction "GND_10") (pintype "power_in"))
      (node (ref "U3") (pin "15") (pinfunction "GND_15") (pintype "power_in"))
      (node (ref "U3") (pin "21") (pinfunction "GND_21") (pintype "power_in"))
      (node (ref "U3") (pin "28") (pinfunction "GND_28") (pintype "power_in"))
      (node (ref "U3") (pin "34") (pinfunction "GND_34") (pintype "power_in"))
      (node (ref "U3") (pin "39") (pinfunction "GND_39") (pintype "power_in"))
      (node (ref "U3") (pin "4") (pinfunction "GND_4") (pintype "power_in"))
      (node (ref "U3") (pin "45") (pinfunction "GND_45") (pintype "power_in"))
      (node (ref "U4") (pin "1") (pinfunction "1DIR_1") (pintype "passive"))
      (node (ref "U4") (pin "10") (pinfunction "GND_10") (pintype "power_in"))
      (node (ref "U4") (pin "15") (pinfunction "GND_15") (pintype "power_in"))
      (node (ref "U4") (pin "21") (pinfunction "GND_21") (pintype "power_in"))
      (node (ref "U4") (pin "25") (pinfunction "~{2OE}_25") (pintype "passive"))
      (node (ref "U4") (pin "28") (pinfunction "GND_28") (pintype "power_in"))
      (node (ref "U4") (pin "34") (pinfunction "GND_34") (pintype "power_in"))
      (node (ref "U4") (pin "39") (pinfunction "GND_39") (pintype "power_in"))
      (node (ref "U4") (pin "4") (pinfunction "GND_4") (pintype "power_in"))
      (node (ref "U4") (pin "45") (pinfunction "GND_45") (pintype "power_in"))
      (node (ref "U4") (pin "48") (pinfunction "~{1OE}_48") (pintype "passive"))
    )
    (net (code "129") (name "unconnected-(CN1-AA24-PadB31)") (class "Default")
      (node (ref "CN1") (pin "B31") (pinfunction "AA24_B31") (pintype "passive"))
    )
    (net (code "130") (name "unconnected-(CN1-AA25-PadA31)") (class "Default")
      (node (ref "CN1") (pin "A31") (pinfunction "AA25_A31") (pintype "passive"))
    )
    (net (code "131") (name "unconnected-(CN1-CRTG0-PadA30)") (class "Default")
      (node (ref "CN1") (pin "A30") (pinfunction "CRTG0_A30") (pintype "passive"))
    )
    (net (code "132") (name "unconnected-(CN1-CRTG1-PadB30)") (class "Default")
      (node (ref "CN1") (pin "B30") (pinfunction "CRTG1_B30") (pintype "passive"))
    )
    (net (code "133") (name "unconnected-(CN1-DBCK-PadB5)") (class "Default")
      (node (ref "CN1") (pin "B5") (pinfunction "DBCK_B5") (pintype "passive"))
    )
    (net (code "134") (name "unconnected-(CN1-DLRCLK-PadB6)") (class "Default")
      (node (ref "CN1") (pin "B6") (pinfunction "DLRCLK_B6") (pintype "passive"))
    )
    (net (code "135") (name "unconnected-(CN1-DOTCLK-PadA28)") (class "Default")
      (node (ref "CN1") (pin "A28") (pinfunction "DOTCLK_A28") (pintype "passive"))
    )
    (net (code "136") (name "unconnected-(CN1-DSD-PadB4)") (class "Default")
      (node (ref "CN1") (pin "B4") (pinfunction "DSD_B4") (pintype "passive"))
    )
    (net (code "137") (name "unconnected-(CN1-ECBG1-PadB9)") (class "Default")
      (node (ref "CN1") (pin "B9") (pinfunction "ECBG1_B9") (pintype "passive"))
    )
    (net (code "138") (name "unconnected-(CN1-ECBG3-PadB10)") (class "Default")
      (node (ref "CN1") (pin "B10") (pinfunction "ECBG3_B10") (pintype "passive"))
    )
    (net (code "139") (name "unconnected-(CN1-ECBG5-PadB11)") (class "Default")
      (node (ref "CN1") (pin "B11") (pinfunction "ECBG5_B11") (pintype "passive"))
    )
    (net (code "140") (name "unconnected-(CN1-EXBG0-PadA9)") (class "Default")
      (node (ref "CN1") (pin "A9") (pinfunction "EXBG0_A9") (pintype "passive"))
    )
    (net (code "141") (name "unconnected-(CN1-EXBG2-PadA10)") (class "Default")
      (node (ref "CN1") (pin "A10") (pinfunction "EXBG2_A10") (pintype "passive"))
    )
    (net (code "142") (name "unconnected-(CN1-EXBG4-PadA11)") (class "Default")
      (node (ref "CN1") (pin "A11") (pinfunction "EXBG4_A11") (pintype "passive"))
    )
    (net (code "143") (name "unconnected-(CN1-EXBG6-PadA12)") (class "Default")
      (node (ref "CN1") (pin "A12") (pinfunction "EXBG6_A12") (pintype "passive"))
    )
    (net (code "144") (name "unconnected-(CN1-EXBG7-PadB12)") (class "Default")
      (node (ref "CN1") (pin "B12") (pinfunction "EXBG7_B12") (pintype "passive"))
    )
    (net (code "145") (name "unconnected-(CN1-EXBG8-PadA14)") (class "Default")
      (node (ref "CN1") (pin "A14") (pinfunction "EXBG8_A14") (pintype "passive"))
    )
    (net (code "146") (name "unconnected-(CN1-EXBG9-PadB14)") (class "Default")
      (node (ref "CN1") (pin "B14") (pinfunction "EXBG9_B14") (pintype "passive"))
    )
    (net (code "147") (name "unconnected-(CN1-EXBG10-PadA15)") (class "Default")
      (node (ref "CN1") (pin "A15") (pinfunction "EXBG10_A15") (pintype "passive"))
    )
    (net (code "148") (name "unconnected-(CN1-EXBG11-PadB15)") (class "Default")
      (node (ref "CN1") (pin "B15") (pinfunction "EXBG11_B15") (pintype "passive"))
    )
    (net (code "149") (name "unconnected-(CN1-EXBG12-PadA16)") (class "Default")
      (node (ref "CN1") (pin "A16") (pinfunction "EXBG12_A16") (pintype "passive"))
    )
    (net (code "150") (name "unconnected-(CN1-EXBG13-PadB16)") (class "Default")
      (node (ref "CN1") (pin "B16") (pinfunction "EXBG13_B16") (pintype "passive"))
    )
    (net (code "151") (name "unconnected-(CN1-EXBG14-PadA17)") (class "Default")
      (node (ref "CN1") (pin "A17") (pinfunction "EXBG14_A17") (pintype "passive"))
    )
    (net (code "152") (name "unconnected-(CN1-EXBG15-PadB17)") (class "Default")
      (node (ref "CN1") (pin "B17") (pinfunction "EXBG15_B17") (pintype "passive"))
    )
    (net (code "153") (name "unconnected-(CN1-EXBG16-PadA19)") (class "Default")
      (node (ref "CN1") (pin "A19") (pinfunction "EXBG16_A19") (pintype "passive"))
    )
    (net (code "154") (name "unconnected-(CN1-EXBG17-PadB19)") (class "Default")
      (node (ref "CN1") (pin "B19") (pinfunction "EXBG17_B19") (pintype "passive"))
    )
    (net (code "155") (name "unconnected-(CN1-EXBG18-PadA20)") (class "Default")
      (node (ref "CN1") (pin "A20") (pinfunction "EXBG18_A20") (pintype "passive"))
    )
    (net (code "156") (name "unconnected-(CN1-EXBG19-PadB20)") (class "Default")
      (node (ref "CN1") (pin "B20") (pinfunction "EXBG19_B20") (pintype "passive"))
    )
    (net (code "157") (name "unconnected-(CN1-EXBG20-PadA21)") (class "Default")
      (node (ref "CN1") (pin "A21") (pinfunction "EXBG20_A21") (pintype "passive"))
    )
    (net (code "158") (name "unconnected-(CN1-EXBG21-PadB21)") (class "Default")
      (node (ref "CN1") (pin "B21") (pinfunction "EXBG21_B21") (pintype "passive"))
    )
    (net (code "159") (name "unconnected-(CN1-EXBG22-PadA22)") (class "Default")
      (node (ref "CN1") (pin "A22") (pinfunction "EXBG22_A22") (pintype "passive"))
    )
    (net (code "160") (name "unconnected-(CN1-EXBG23-PadB22)") (class "Default")
      (node (ref "CN1") (pin "B22") (pinfunction "EXBG23_B22") (pintype "passive"))
    )
    (net (code "161") (name "unconnected-(CN1-~{COPRES}-PadA66)") (class "Default")
      (node (ref "CN1") (pin "A66") (pinfunction "~{COPRES}_A66") (pintype "passive"))
    )
    (net (code "162") (name "unconnected-(CN1-~{EXD}N-PadA24)") (class "Default")
      (node (ref "CN1") (pin "A24") (pinfunction "~{EXD}N_A24") (pintype "passive"))
    )
    (net (code "163") (name "unconnected-(CN1-~{EXLAT}-PadA25)") (class "Default")
      (node (ref "CN1") (pin "A25") (pinfunction "~{EXLAT}_A25") (pintype "passive"))
    )
    (net (code "164") (name "unconnected-(CN1-~{EXSL}-PadB25)") (class "Default")
      (node (ref "CN1") (pin "B25") (pinfunction "~{EXSL}_B25") (pintype "passive"))
    )
    (net (code "165") (name "unconnected-(CN1-~{EXSYNC}-PadB28)") (class "Default")
      (node (ref "CN1") (pin "B28") (pinfunction "~{EXSYNC}_B28") (pintype "passive"))
    )
    (net (code "166") (name "unconnected-(CN1-~{HSYNC}-PadA26)") (class "Default")
      (node (ref "CN1") (pin "A26") (pinfunction "~{HSYNC}_A26") (pintype "passive"))
    )
    (net (code "167") (name "unconnected-(CN1-~{MPEGON}-PadB24)") (class "Default")
      (node (ref "CN1") (pin "B24") (pinfunction "~{MPEGON}_B24") (pintype "passive"))
    )
    (net (code "168") (name "unconnected-(CN1-~{VSYNC}-PadB26)") (class "Default")
      (node (ref "CN1") (pin "B26") (pinfunction "~{VSYNC}_B26") (pintype "passive"))
    )
    (net (code "169") (name "unconnected-(U1-2A5-Pad30)") (class "Default")
      (node (ref "U1") (pin "30") (pinfunction "2A5_30") (pintype "passive"))
    )
    (net (code "170") (name "unconnected-(U1-2B5-Pad19)") (class "Default")
      (node (ref "U1") (pin "19") (pinfunction "2B5_19") (pintype "passive"))
    )
    (net (code "171") (name "unconnected-(U4-2A5-Pad30)") (class "Default")
      (node (ref "U4") (pin "30") (pinfunction "2A5_30") (pintype "passive"))
    )
    (net (code "172") (name "unconnected-(U4-2A6-Pad29)") (class "Default")
      (node (ref "U4") (pin "29") (pinfunction "2A6_29") (pintype "passive"))
    )
    (net (code "173") (name "unconnected-(U4-2B5-Pad19)") (class "Default")
      (node (ref "U4") (pin "19") (pinfunction "2B5_19") (pintype "passive"))
    )
    (net (code "174") (name "unconnected-(U4-2B6-Pad20)") (class "Default")
      (node (ref "U4") (pin "20") (pinfunction "2B6_20") (pintype "passive"))
    )
    (net (code "175") (name "unconnected-(U5D-IO,_DIFFIO_B13p-PadK9)") (class "Default")
      (node (ref "U5") (pin "K9") (pinfunction "IO,_DIFFIO_B13p_K9") (pintype "bidirectional"))
    )
    (net (code "176") (name "unconnected-(U5D-IO,_DIFFIO_B18n-PadL10)") (class "Default")
      (node (ref "U5") (pin "L10") (pinfunction "IO,_DIFFIO_B18n_L10") (pintype "bidirectional"))
    )
    (net (code "177") (name "unconnected-(U5D-IO,_DIFFIO_B18p-PadK10)") (class "Default")
      (node (ref "U5") (pin "K10") (pinfunction "IO,_DIFFIO_B18p_K10") (pintype "bidirectional"))
    )
    (net (code "178") (name "unconnected-(U5D-IO,_DIFFIO_B21n-PadL11)") (class "Default")
      (node (ref "U5") (pin "L11") (pinfunction "IO,_DIFFIO_B21n_L11") (pintype "bidirectional"))
    )
    (net (code "179") (name "unconnected-(U5D-IO,_DIFFIO_B22p-PadM11)") (class "Default")
      (node (ref "U5") (pin "M11") (pinfunction "IO,_DIFFIO_B22p_M11") (pintype "bidirectional"))
    )
    (net (code "180") (name "unconnected-(U5E-IO-PadK11)") (class "Default")
      (node (ref "U5") (pin "K11") (pinfunction "IO_K11") (pintype "bidirectional"))
    )
  )
)
